# 5_ZeroCrossingDetector.net
KiCad netlist of a schematic drawn in Altium Designer
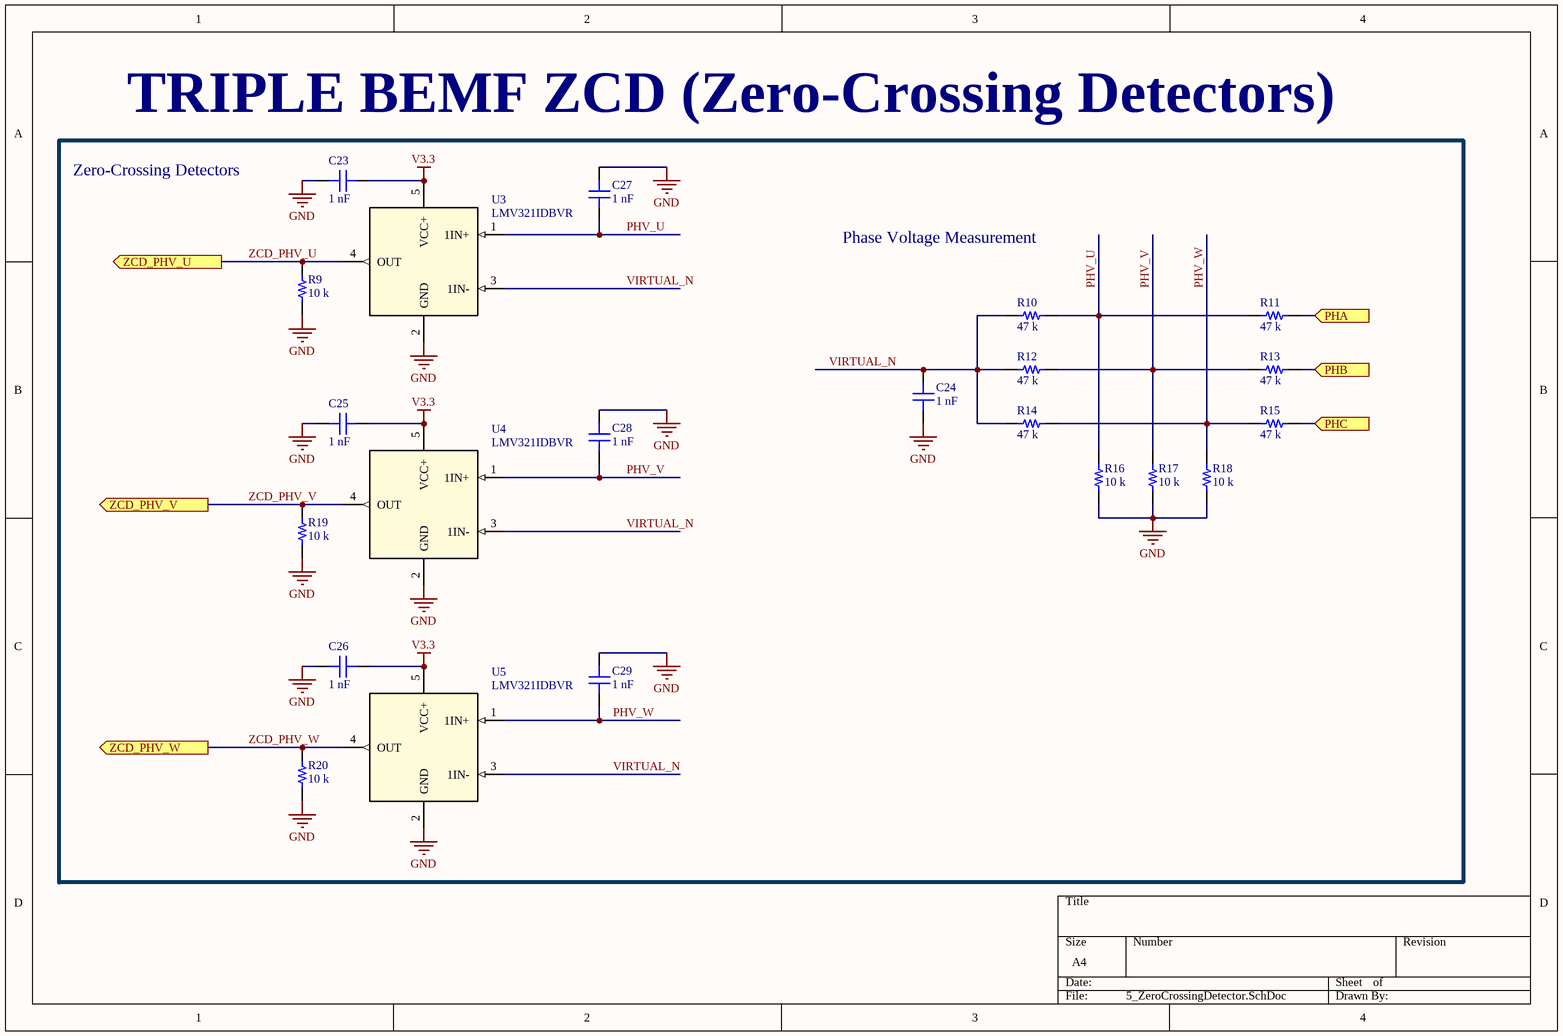
[diagram p0: 5_ZeroCrossingDetector.SchDoc]

(export (version "E")
  (design (tool "Eeschema 10.0.6"))
  (components
    (comp (ref "C23")
      (value "1 nF")
      (footprint "CAP 0805_2012")
      (description "CAP CER 0.1UF 50V X7R 0805")
      (fields (field (name "PART NUMBER") "CC0805MRX7R9BB104") (field (name "MANUFACTURER") "Yageo"))
      (libsource (lib "Celestial Altium Library - altium_library") (part "Capacitor"))
    )
    (comp (ref "C24")
      (value "1 nF")
      (footprint "CAP 0805_2012")
      (description "CAP CER 0.1UF 50V X7R 0805")
      (fields (field (name "PART NUMBER") "CC0805MRX7R9BB104") (field (name "MANUFACTURER") "Yageo"))
      (libsource (lib "Celestial Altium Library - altium_library") (part "Capacitor"))
    )
    (comp (ref "C25")
      (value "1 nF")
      (footprint "CAP 0805_2012")
      (description "CAP CER 0.1UF 50V X7R 0805")
      (fields (field (name "PART NUMBER") "CC0805MRX7R9BB104") (field (name "MANUFACTURER") "Yageo"))
      (libsource (lib "Celestial Altium Library - altium_library") (part "Capacitor"))
    )
    (comp (ref "C26")
      (value "1 nF")
      (footprint "CAP 0805_2012")
      (description "CAP CER 0.1UF 50V X7R 0805")
      (fields (field (name "PART NUMBER") "CC0805MRX7R9BB104") (field (name "MANUFACTURER") "Yageo"))
      (libsource (lib "Celestial Altium Library - altium_library") (part "Capacitor"))
    )
    (comp (ref "C27")
      (value "1 nF")
      (footprint "CAP 0805_2012")
      (description "CAP CER 0.1UF 50V X7R 0805")
      (fields (field (name "PART NUMBER") "CC0805MRX7R9BB104") (field (name "MANUFACTURER") "Yageo"))
      (libsource (lib "Celestial Altium Library - altium_library") (part "Capacitor"))
    )
    (comp (ref "C28")
      (value "1 nF")
      (footprint "CAP 0805_2012")
      (description "CAP CER 0.1UF 50V X7R 0805")
      (fields (field (name "PART NUMBER") "CC0805MRX7R9BB104") (field (name "MANUFACTURER") "Yageo"))
      (libsource (lib "Celestial Altium Library - altium_library") (part "Capacitor"))
    )
    (comp (ref "C29")
      (value "1 nF")
      (footprint "CAP 0805_2012")
      (description "CAP CER 0.1UF 50V X7R 0805")
      (fields (field (name "PART NUMBER") "CC0805MRX7R9BB104") (field (name "MANUFACTURER") "Yageo"))
      (libsource (lib "Celestial Altium Library - altium_library") (part "Capacitor"))
    )
    (comp (ref "R9")
      (value "10 k")
      (footprint "RES 0805_2012")
      (description "RES SMD 200K OHM 5% 1/8W 0805")
      (fields (field (name "PART NUMBER") "CR0805-JW-204ELF") (field (name "MANUFACTURER") "Bourns Inc."))
      (libsource (lib "Celestial Altium Library - altium_library") (part "Resistor"))
    )
    (comp (ref "R10")
      (value "47 k")
      (footprint "RES 0805_2012")
      (description "RES SMD 200K OHM 5% 1/8W 0805")
      (fields (field (name "PART NUMBER") "CR0805-JW-204ELF") (field (name "MANUFACTURER") "Bourns Inc."))
      (libsource (lib "Celestial Altium Library - altium_library") (part "Resistor"))
    )
    (comp (ref "R11")
      (value "47 k")
      (footprint "RES 0805_2012")
      (description "RES SMD 200K OHM 5% 1/8W 0805")
      (fields (field (name "PART NUMBER") "CR0805-JW-204ELF") (field (name "MANUFACTURER") "Bourns Inc."))
      (libsource (lib "Celestial Altium Library - altium_library") (part "Resistor"))
    )
    (comp (ref "R12")
      (value "47 k")
      (footprint "RES 0805_2012")
      (description "RES SMD 200K OHM 5% 1/8W 0805")
      (fields (field (name "PART NUMBER") "CR0805-JW-204ELF") (field (name "MANUFACTURER") "Bourns Inc."))
      (libsource (lib "Celestial Altium Library - altium_library") (part "Resistor"))
    )
    (comp (ref "R13")
      (value "47 k")
      (footprint "RES 0805_2012")
      (description "RES SMD 200K OHM 5% 1/8W 0805")
      (fields (field (name "PART NUMBER") "CR0805-JW-204ELF") (field (name "MANUFACTURER") "Bourns Inc."))
      (libsource (lib "Celestial Altium Library - altium_library") (part "Resistor"))
    )
    (comp (ref "R14")
      (value "47 k")
      (footprint "RES 0805_2012")
      (description "RES SMD 200K OHM 5% 1/8W 0805")
      (fields (field (name "PART NUMBER") "CR0805-JW-204ELF") (field (name "MANUFACTURER") "Bourns Inc."))
      (libsource (lib "Celestial Altium Library - altium_library") (part "Resistor"))
    )
    (comp (ref "R15")
      (value "47 k")
      (footprint "RES 0805_2012")
      (description "RES SMD 200K OHM 5% 1/8W 0805")
      (fields (field (name "PART NUMBER") "CR0805-JW-204ELF") (field (name "MANUFACTURER") "Bourns Inc."))
      (libsource (lib "Celestial Altium Library - altium_library") (part "Resistor"))
    )
    (comp (ref "R16")
      (value "10 k")
      (footprint "RES 0805_2012")
      (description "RES SMD 200K OHM 5% 1/8W 0805")
      (fields (field (name "PART NUMBER") "CR0805-JW-204ELF") (field (name "MANUFACTURER") "Bourns Inc."))
      (libsource (lib "Celestial Altium Library - altium_library") (part "Resistor"))
    )
    (comp (ref "R17")
      (value "10 k")
      (footprint "RES 0805_2012")
      (description "RES SMD 200K OHM 5% 1/8W 0805")
      (fields (field (name "PART NUMBER") "CR0805-JW-204ELF") (field (name "MANUFACTURER") "Bourns Inc."))
      (libsource (lib "Celestial Altium Library - altium_library") (part "Resistor"))
    )
    (comp (ref "R18")
      (value "10 k")
      (footprint "RES 0805_2012")
      (description "RES SMD 200K OHM 5% 1/8W 0805")
      (fields (field (name "PART NUMBER") "CR0805-JW-204ELF") (field (name "MANUFACTURER") "Bourns Inc."))
      (libsource (lib "Celestial Altium Library - altium_library") (part "Resistor"))
    )
    (comp (ref "R19")
      (value "10 k")
      (footprint "RES 0805_2012")
      (description "RES SMD 200K OHM 5% 1/8W 0805")
      (fields (field (name "PART NUMBER") "CR0805-JW-204ELF") (field (name "MANUFACTURER") "Bourns Inc."))
      (libsource (lib "Celestial Altium Library - altium_library") (part "Resistor"))
    )
    (comp (ref "R20")
      (value "10 k")
      (footprint "RES 0805_2012")
      (description "RES SMD 200K OHM 5% 1/8W 0805")
      (fields (field (name "PART NUMBER") "CR0805-JW-204ELF") (field (name "MANUFACTURER") "Bourns Inc."))
      (libsource (lib "Celestial Altium Library - altium_library") (part "Resistor"))
    )
    (comp (ref "U3")
      (value "LMV321IDBVR")
      (footprint "DBV5")
      (description "No Description Available")
      (fields (field (name "COPYRIGHT") "Copyright (C) 2023 Ultra Librarian. All rights reserved."))
      (libsource (lib "LMV321IDBVR") (part "LMV321IDBVR"))
    )
    (comp (ref "U4")
      (value "LMV321IDBVR")
      (footprint "DBV5")
      (description "No Description Available")
      (fields (field (name "COPYRIGHT") "Copyright (C) 2023 Ultra Librarian. All rights reserved."))
      (libsource (lib "LMV321IDBVR") (part "LMV321IDBVR"))
    )
    (comp (ref "U5")
      (value "LMV321IDBVR")
      (footprint "DBV5")
      (description "No Description Available")
      (fields (field (name "COPYRIGHT") "Copyright (C) 2023 Ultra Librarian. All rights reserved."))
      (libsource (lib "LMV321IDBVR") (part "LMV321IDBVR"))
    )
  )
  (nets
    (net (code "1") (name "/PHA") (class "Default")
      (node (ref "R11") (pin "1") (pinfunction "1_1") (pintype "passive"))
    )
    (net (code "2") (name "/PHB") (class "Default")
      (node (ref "R13") (pin "1") (pinfunction "1_1") (pintype "passive"))
    )
    (net (code "3") (name "/PHC") (class "Default")
      (node (ref "R15") (pin "1") (pinfunction "1_1") (pintype "passive"))
    )
    (net (code "4") (name "/PHV_U") (class "Default")
      (node (ref "C27") (pin "2") (pinfunction "2_2") (pintype "passive"))
      (node (ref "R10") (pin "1") (pinfunction "1_1") (pintype "passive"))
      (node (ref "R11") (pin "2") (pinfunction "2_2") (pintype "passive"))
      (node (ref "R16") (pin "1") (pinfunction "1_1") (pintype "passive"))
      (node (ref "U3") (pin "1") (pinfunction "1IN+_1") (pintype "input"))
    )
    (net (code "5") (name "/PHV_V") (class "Default")
      (node (ref "C28") (pin "2") (pinfunction "2_2") (pintype "passive"))
      (node (ref "R12") (pin "1") (pinfunction "1_1") (pintype "passive"))
      (node (ref "R13") (pin "2") (pinfunction "2_2") (pintype "passive"))
      (node (ref "R17") (pin "1") (pinfunction "1_1") (pintype "passive"))
      (node (ref "U4") (pin "1") (pinfunction "1IN+_1") (pintype "input"))
    )
    (net (code "6") (name "/PHV_W") (class "Default")
      (node (ref "C29") (pin "2") (pinfunction "2_2") (pintype "passive"))
      (node (ref "R14") (pin "1") (pinfunction "1_1") (pintype "passive"))
      (node (ref "R15") (pin "2") (pinfunction "2_2") (pintype "passive"))
      (node (ref "R18") (pin "1") (pinfunction "1_1") (pintype "passive"))
      (node (ref "U5") (pin "1") (pinfunction "1IN+_1") (pintype "input"))
    )
    (net (code "7") (name "/VIRTUAL_N") (class "Default")
      (node (ref "C24") (pin "2") (pinfunction "2_2") (pintype "passive"))
      (node (ref "R10") (pin "2") (pinfunction "2_2") (pintype "passive"))
      (node (ref "R12") (pin "2") (pinfunction "2_2") (pintype "passive"))
      (node (ref "R14") (pin "2") (pinfunction "2_2") (pintype "passive"))
      (node (ref "U3") (pin "3") (pinfunction "1IN-_3") (pintype "input"))
      (node (ref "U4") (pin "3") (pinfunction "1IN-_3") (pintype "input"))
      (node (ref "U5") (pin "3") (pinfunction "1IN-_3") (pintype "input"))
    )
    (net (code "8") (name "/ZCD_PHV_U") (class "Default")
      (node (ref "R9") (pin "1") (pinfunction "1_1") (pintype "passive"))
      (node (ref "U3") (pin "4") (pinfunction "OUT_4") (pintype "output"))
    )
    (net (code "9") (name "/ZCD_PHV_V") (class "Default")
      (node (ref "R19") (pin "1") (pinfunction "1_1") (pintype "passive"))
      (node (ref "U4") (pin "4") (pinfunction "OUT_4") (pintype "output"))
    )
    (net (code "10") (name "/ZCD_PHV_W") (class "Default")
      (node (ref "R20") (pin "1") (pinfunction "1_1") (pintype "passive"))
      (node (ref "U5") (pin "4") (pinfunction "OUT_4") (pintype "output"))
    )
    (net (code "11") (name "GND") (class "Default")
      (node (ref "C23") (pin "2") (pinfunction "2_2") (pintype "passive"))
      (node (ref "C24") (pin "1") (pinfunction "1_1") (pintype "passive"))
      (node (ref "C25") (pin "2") (pinfunction "2_2") (pintype "passive"))
      (node (ref "C26") (pin "2") (pinfunction "2_2") (pintype "passive"))
      (node (ref "C27") (pin "1") (pinfunction "1_1") (pintype "passive"))
      (node (ref "C28") (pin "1") (pinfunction "1_1") (pintype "passive"))
      (node (ref "C29") (pin "1") (pinfunction "1_1") (pintype "passive"))
      (node (ref "R16") (pin "2") (pinfunction "2_2") (pintype "passive"))
      (node (ref "R17") (pin "2") (pinfunction "2_2") (pintype "passive"))
      (node (ref "R18") (pin "2") (pinfunction "2_2") (pintype "passive"))
      (node (ref "R19") (pin "2") (pinfunction "2_2") (pintype "passive"))
      (node (ref "R20") (pin "2") (pinfunction "2_2") (pintype "passive"))
      (node (ref "R9") (pin "2") (pinfunction "2_2") (pintype "passive"))
      (node (ref "U3") (pin "2") (pinfunction "GND_2") (pintype "power_in"))
      (node (ref "U4") (pin "2") (pinfunction "GND_2") (pintype "power_in"))
      (node (ref "U5") (pin "2") (pinfunction "GND_2") (pintype "power_in"))
    )
    (net (code "12") (name "V3.3") (class "Default")
      (node (ref "C23") (pin "1") (pinfunction "1_1") (pintype "passive"))
      (node (ref "C25") (pin "1") (pinfunction "1_1") (pintype "passive"))
      (node (ref "C26") (pin "1") (pinfunction "1_1") (pintype "passive"))
      (node (ref "U3") (pin "5") (pinfunction "VCC+_5") (pintype "power_in"))
      (node (ref "U4") (pin "5") (pinfunction "VCC+_5") (pintype "power_in"))
      (node (ref "U5") (pin "5") (pinfunction "VCC+_5") (pintype "power_in"))
    )
  )
)
